# FPGA_PWR.net
KiCad netlist of a schematic drawn in Altium Designer
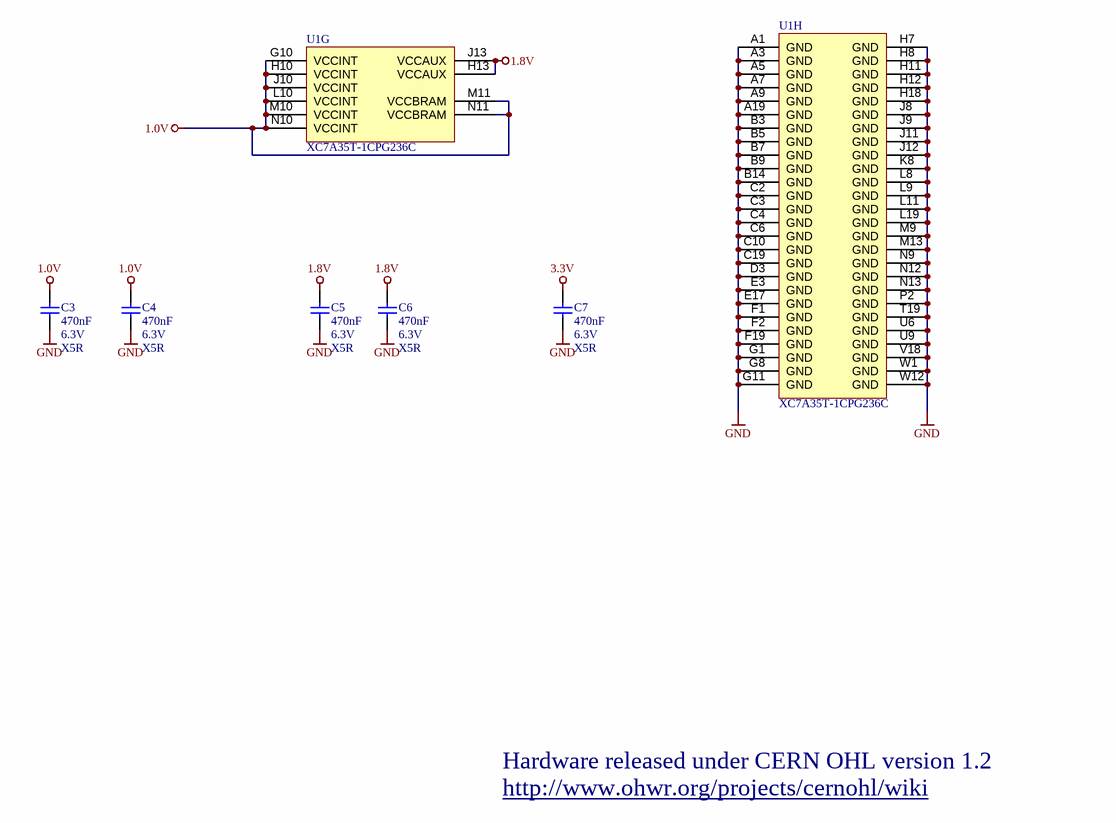
[diagram p0: FPGA_PWR.SchDoc]

(export (version "E")
  (design (tool "Eeschema 10.0.6"))
  (components
    (comp (ref "C3")
      (value "470nF")
      (footprint "CAPC0603X33N")
      (description "KON 470nF X5R 6.3V SMD 20%")
      (fields
        (field (name "VOLTAGE") "6.3V")
        (field (name "TECHNOLOGY") "X5R")
        (field (name "TOLERANCE") "20%")
      )
      (libsource (lib "TE") (part "CAP-NP"))
    )
    (comp (ref "C4")
      (value "470nF")
      (footprint "CAPC0603X33N")
      (description "KON 470nF X5R 6.3V SMD 20%")
      (fields
        (field (name "VOLTAGE") "6.3V")
        (field (name "TECHNOLOGY") "X5R")
        (field (name "TOLERANCE") "20%")
      )
      (libsource (lib "TE") (part "CAP-NP"))
    )
    (comp (ref "C5")
      (value "470nF")
      (footprint "CAPC0603X33N")
      (description "KON 470nF X5R 6.3V SMD 20%")
      (fields
        (field (name "VOLTAGE") "6.3V")
        (field (name "TECHNOLOGY") "X5R")
        (field (name "TOLERANCE") "20%")
      )
      (libsource (lib "TE") (part "CAP-NP"))
    )
    (comp (ref "C6")
      (value "470nF")
      (footprint "CAPC0603X33N")
      (description "KON 470nF X5R 6.3V SMD 20%")
      (fields
        (field (name "VOLTAGE") "6.3V")
        (field (name "TECHNOLOGY") "X5R")
        (field (name "TOLERANCE") "20%")
      )
      (libsource (lib "TE") (part "CAP-NP"))
    )
    (comp (ref "C7")
      (value "470nF")
      (footprint "CAPC0603X33N")
      (description "KON 470nF X5R 6.3V SMD 20%")
      (fields
        (field (name "VOLTAGE") "6.3V")
        (field (name "TECHNOLOGY") "X5R")
        (field (name "TOLERANCE") "20%")
      )
      (libsource (lib "TE") (part "CAP-NP"))
    )
    (comp (ref "U1")
      (value "XC7A35T-1CPG236C")
      (footprint "XC7AxxT-CPG236")
      (libsource (lib "TE") (part "XC7A35T-CPG236"))
    )
  )
  (nets
    (net (code "1") (name "1.0V") (class "Default")
      (node (ref "C3") (pin "1") (pinfunction "1_1") (pintype "passive"))
      (node (ref "C4") (pin "1") (pinfunction "1_1") (pintype "passive"))
      (node (ref "U1") (pin "G10") (pinfunction "VCCINT_G10") (pintype "power_in"))
      (node (ref "U1") (pin "H10") (pinfunction "VCCINT_H10") (pintype "power_in"))
      (node (ref "U1") (pin "J10") (pinfunction "VCCINT_J10") (pintype "power_in"))
      (node (ref "U1") (pin "L10") (pinfunction "VCCINT_L10") (pintype "power_in"))
      (node (ref "U1") (pin "M10") (pinfunction "VCCINT_M10") (pintype "power_in"))
      (node (ref "U1") (pin "M11") (pinfunction "VCCBRAM_M11") (pintype "power_in"))
      (node (ref "U1") (pin "N10") (pinfunction "VCCINT_N10") (pintype "power_in"))
      (node (ref "U1") (pin "N11") (pinfunction "VCCBRAM_N11") (pintype "power_in"))
    )
    (net (code "2") (name "1.8V") (class "Default")
      (node (ref "C5") (pin "1") (pinfunction "1_1") (pintype "passive"))
      (node (ref "C6") (pin "1") (pinfunction "1_1") (pintype "passive"))
      (node (ref "U1") (pin "H13") (pinfunction "VCCAUX_H13") (pintype "power_in"))
      (node (ref "U1") (pin "J13") (pinfunction "VCCAUX_J13") (pintype "power_in"))
    )
    (net (code "3") (name "3.3V") (class "Default")
      (node (ref "C7") (pin "1") (pinfunction "1_1") (pintype "passive"))
    )
    (net (code "4") (name "GND") (class "Default")
      (node (ref "C3") (pin "2") (pinfunction "2_2") (pintype "passive"))
      (node (ref "C4") (pin "2") (pinfunction "2_2") (pintype "passive"))
      (node (ref "C5") (pin "2") (pinfunction "2_2") (pintype "passive"))
      (node (ref "C6") (pin "2") (pinfunction "2_2") (pintype "passive"))
      (node (ref "C7") (pin "2") (pinfunction "2_2") (pintype "passive"))
      (node (ref "U1") (pin "A1") (pinfunction "GND_A1") (pintype "power_in"))
      (node (ref "U1") (pin "A19") (pinfunction "GND_A19") (pintype "power_in"))
      (node (ref "U1") (pin "A3") (pinfunction "GND_A3") (pintype "power_in"))
      (node (ref "U1") (pin "A5") (pinfunction "GND_A5") (pintype "power_in"))
      (node (ref "U1") (pin "A7") (pinfunction "GND_A7") (pintype "power_in"))
      (node (ref "U1") (pin "A9") (pinfunction "GND_A9") (pintype "power_in"))
      (node (ref "U1") (pin "B14") (pinfunction "GND_B14") (pintype "power_in"))
      (node (ref "U1") (pin "B3") (pinfunction "GND_B3") (pintype "power_in"))
      (node (ref "U1") (pin "B5") (pinfunction "GND_B5") (pintype "power_in"))
      (node (ref "U1") (pin "B7") (pinfunction "GND_B7") (pintype "power_in"))
      (node (ref "U1") (pin "B9") (pinfunction "GND_B9") (pintype "power_in"))
      (node (ref "U1") (pin "C10") (pinfunction "GND_C10") (pintype "power_in"))
      (node (ref "U1") (pin "C19") (pinfunction "GND_C19") (pintype "power_in"))
      (node (ref "U1") (pin "C2") (pinfunction "GND_C2") (pintype "power_in"))
      (node (ref "U1") (pin "C3") (pinfunction "GND_C3") (pintype "power_in"))
      (node (ref "U1") (pin "C4") (pinfunction "GND_C4") (pintype "power_in"))
      (node (ref "U1") (pin "C6") (pinfunction "GND_C6") (pintype "power_in"))
      (node (ref "U1") (pin "D3") (pinfunction "GND_D3") (pintype "power_in"))
      (node (ref "U1") (pin "E17") (pinfunction "GND_E17") (pintype "power_in"))
      (node (ref "U1") (pin "E3") (pinfunction "GND_E3") (pintype "power_in"))
      (node (ref "U1") (pin "F1") (pinfunction "GND_F1") (pintype "power_in"))
      (node (ref "U1") (pin "F19") (pinfunction "GND_F19") (pintype "power_in"))
      (node (ref "U1") (pin "F2") (pinfunction "GND_F2") (pintype "power_in"))
      (node (ref "U1") (pin "G1") (pinfunction "GND_G1") (pintype "power_in"))
      (node (ref "U1") (pin "G11") (pinfunction "GND_G11") (pintype "power_in"))
      (node (ref "U1") (pin "G8") (pinfunction "GND_G8") (pintype "power_in"))
      (node (ref "U1") (pin "H11") (pinfunction "GND_H11") (pintype "power_in"))
      (node (ref "U1") (pin "H12") (pinfunction "GND_H12") (pintype "power_in"))
      (node (ref "U1") (pin "H18") (pinfunction "GND_H18") (pintype "power_in"))
      (node (ref "U1") (pin "H7") (pinfunction "GND_H7") (pintype "power_in"))
      (node (ref "U1") (pin "H8") (pinfunction "GND_H8") (pintype "power_in"))
      (node (ref "U1") (pin "J11") (pinfunction "GND_J11") (pintype "power_in"))
      (node (ref "U1") (pin "J12") (pinfunction "GND_J12") (pintype "power_in"))
      (node (ref "U1") (pin "J8") (pinfunction "GND_J8") (pintype "power_in"))
      (node (ref "U1") (pin "J9") (pinfunction "GND_J9") (pintype "power_in"))
      (node (ref "U1") (pin "K8") (pinfunction "GND_K8") (pintype "power_in"))
      (node (ref "U1") (pin "L11") (pinfunction "GND_L11") (pintype "power_in"))
      (node (ref "U1") (pin "L19") (pinfunction "GND_L19") (pintype "power_in"))
      (node (ref "U1") (pin "L8") (pinfunction "GND_L8") (pintype "power_in"))
      (node (ref "U1") (pin "L9") (pinfunction "GND_L9") (pintype "power_in"))
      (node (ref "U1") (pin "M13") (pinfunction "GND_M13") (pintype "power_in"))
      (node (ref "U1") (pin "M9") (pinfunction "GND_M9") (pintype "power_in"))
      (node (ref "U1") (pin "N12") (pinfunction "GND_N12") (pintype "power_in"))
      (node (ref "U1") (pin "N13") (pinfunction "GND_N13") (pintype "power_in"))
      (node (ref "U1") (pin "N9") (pinfunction "GND_N9") (pintype "power_in"))
      (node (ref "U1") (pin "P2") (pinfunction "GND_P2") (pintype "power_in"))
      (node (ref "U1") (pin "T19") (pinfunction "GND_T19") (pintype "power_in"))
      (node (ref "U1") (pin "U6") (pinfunction "GND_U6") (pintype "power_in"))
      (node (ref "U1") (pin "U9") (pinfunction "GND_U9") (pintype "power_in"))
      (node (ref "U1") (pin "V18") (pinfunction "GND_V18") (pintype "power_in"))
      (node (ref "U1") (pin "W1") (pinfunction "GND_W1") (pintype "power_in"))
      (node (ref "U1") (pin "W12") (pinfunction "GND_W12") (pintype "power_in"))
    )
  )
)
